# levelshifter.net
KiCad netlist of a schematic drawn in EAGLE
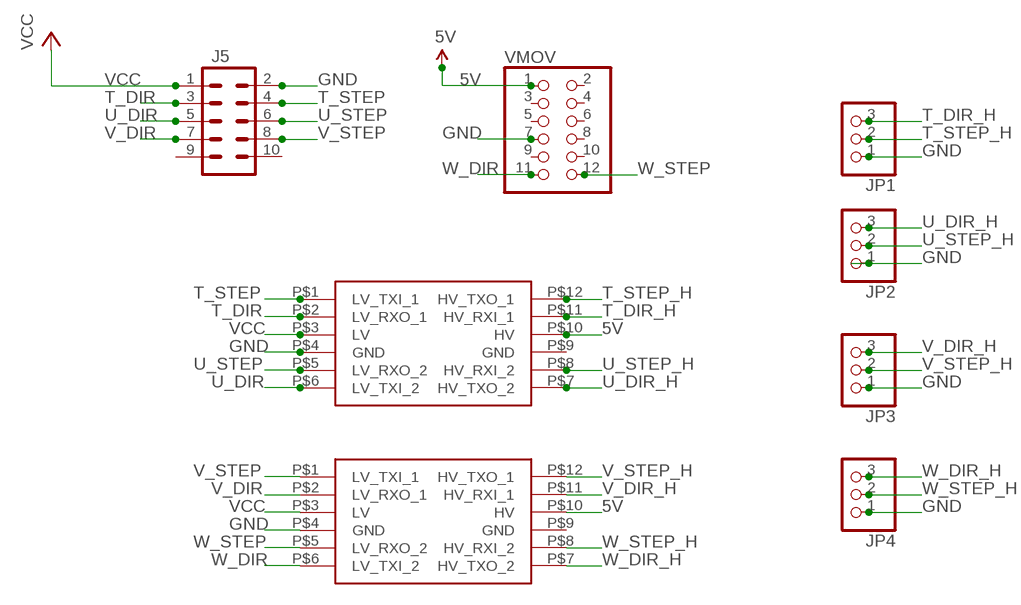
[diagram p0: schematic, sheet 1]

(export (version "E")
  (design (tool "Eeschema 10.0.6"))
  (components
    (comp (ref "CP")
      (value "LOGIC_LEVEL_CONVERTER")
      (footprint "eagle-import:LOGIC_LEVEL_CONVERTER")
      (libsource (lib "eagle-import") (part "LOGIC_LEVEL_CONVERTER"))
    )
    (comp (ref "CP1")
      (value "LOGIC_LEVEL_CONVERTER")
      (footprint "eagle-import:LOGIC_LEVEL_CONVERTER")
      (libsource (lib "eagle-import") (part "LOGIC_LEVEL_CONVERTER"))
    )
    (comp (ref "J5")
      (value "M05X2PTH")
      (footprint "eagle-import:AVR_ICSP")
      (libsource (lib "eagle-import") (part "M05X2PTH"))
    )
    (comp (ref "JP1")
      (value "PINHD-1X3")
      (footprint "eagle-import:1X03")
      (libsource (lib "eagle-import") (part "PINHD-1X3"))
    )
    (comp (ref "JP2")
      (value "PINHD-1X3")
      (footprint "eagle-import:1X03")
      (libsource (lib "eagle-import") (part "PINHD-1X3"))
    )
    (comp (ref "JP3")
      (value "PINHD-1X3")
      (footprint "eagle-import:1X03")
      (libsource (lib "eagle-import") (part "PINHD-1X3"))
    )
    (comp (ref "JP4")
      (value "PINHD-1X3")
      (footprint "eagle-import:1X03")
      (libsource (lib "eagle-import") (part "PINHD-1X3"))
    )
    (comp (ref "VMOV")
      (value "PINHD-2X6")
      (footprint "eagle-import:2X06")
      (libsource (lib "eagle-import") (part "PINHD-2X6"))
    )
  )
  (nets
    (net (code "1") (name "/GND") (class "Default")
      (node (ref "CP") (pin "P$4") (pinfunction "GND_P$4") (pintype "bidirectional"))
      (node (ref "CP1") (pin "P$4") (pinfunction "GND_P$4") (pintype "bidirectional"))
      (node (ref "J5") (pin "2") (pinfunction "2_2") (pintype "passive"))
      (node (ref "JP1") (pin "1") (pinfunction "1_1") (pintype "passive"))
      (node (ref "JP2") (pin "1") (pinfunction "1_1") (pintype "passive"))
      (node (ref "JP3") (pin "1") (pinfunction "1_1") (pintype "passive"))
      (node (ref "JP4") (pin "1") (pinfunction "1_1") (pintype "passive"))
      (node (ref "VMOV") (pin "7") (pinfunction "7_7") (pintype "passive"))
    )
    (net (code "2") (name "/T_DIR") (class "Default")
      (node (ref "CP") (pin "P$2") (pinfunction "LV_RXO_1_P$2") (pintype "bidirectional"))
      (node (ref "J5") (pin "3") (pinfunction "3_3") (pintype "passive"))
    )
    (net (code "3") (name "/T_DIR_H") (class "Default")
      (node (ref "CP") (pin "P$11") (pinfunction "HV_RXI_1_P$11") (pintype "bidirectional"))
      (node (ref "JP1") (pin "3") (pinfunction "3_3") (pintype "passive"))
    )
    (net (code "4") (name "/T_STEP") (class "Default")
      (node (ref "CP") (pin "P$1") (pinfunction "LV_TXI_1_P$1") (pintype "bidirectional"))
      (node (ref "J5") (pin "4") (pinfunction "4_4") (pintype "passive"))
    )
    (net (code "5") (name "/T_STEP_H") (class "Default")
      (node (ref "CP") (pin "P$12") (pinfunction "HV_TXO_1_P$12") (pintype "bidirectional"))
      (node (ref "JP1") (pin "2") (pinfunction "2_2") (pintype "passive"))
    )
    (net (code "6") (name "/U_DIR") (class "Default")
      (node (ref "CP") (pin "P$6") (pinfunction "LV_TXI_2_P$6") (pintype "bidirectional"))
      (node (ref "J5") (pin "5") (pinfunction "5_5") (pintype "passive"))
    )
    (net (code "7") (name "/U_DIR_H") (class "Default")
      (node (ref "CP") (pin "P$7") (pinfunction "HV_TXO_2_P$7") (pintype "bidirectional"))
      (node (ref "JP2") (pin "3") (pinfunction "3_3") (pintype "passive"))
    )
    (net (code "8") (name "/U_STEP") (class "Default")
      (node (ref "CP") (pin "P$5") (pinfunction "LV_RXO_2_P$5") (pintype "bidirectional"))
      (node (ref "J5") (pin "6") (pinfunction "6_6") (pintype "passive"))
    )
    (net (code "9") (name "/U_STEP_H") (class "Default")
      (node (ref "CP") (pin "P$8") (pinfunction "HV_RXI_2_P$8") (pintype "bidirectional"))
      (node (ref "JP2") (pin "2") (pinfunction "2_2") (pintype "passive"))
    )
    (net (code "10") (name "/V_DIR") (class "Default")
      (node (ref "CP1") (pin "P$2") (pinfunction "LV_RXO_1_P$2") (pintype "bidirectional"))
      (node (ref "J5") (pin "7") (pinfunction "7_7") (pintype "passive"))
    )
    (net (code "11") (name "/V_DIR_H") (class "Default")
      (node (ref "CP1") (pin "P$11") (pinfunction "HV_RXI_1_P$11") (pintype "bidirectional"))
      (node (ref "JP3") (pin "3") (pinfunction "3_3") (pintype "passive"))
    )
    (net (code "12") (name "/V_STEP") (class "Default")
      (node (ref "CP1") (pin "P$1") (pinfunction "LV_TXI_1_P$1") (pintype "bidirectional"))
      (node (ref "J5") (pin "8") (pinfunction "8_8") (pintype "passive"))
    )
    (net (code "13") (name "/V_STEP_H") (class "Default")
      (node (ref "CP1") (pin "P$12") (pinfunction "HV_TXO_1_P$12") (pintype "bidirectional"))
      (node (ref "JP3") (pin "2") (pinfunction "2_2") (pintype "passive"))
    )
    (net (code "14") (name "/W_DIR") (class "Default")
      (node (ref "CP1") (pin "P$6") (pinfunction "LV_TXI_2_P$6") (pintype "bidirectional"))
      (node (ref "VMOV") (pin "11") (pinfunction "11_11") (pintype "passive"))
    )
    (net (code "15") (name "/W_DIR_H") (class "Default")
      (node (ref "CP1") (pin "P$7") (pinfunction "HV_TXO_2_P$7") (pintype "bidirectional"))
      (node (ref "JP4") (pin "3") (pinfunction "3_3") (pintype "passive"))
    )
    (net (code "16") (name "/W_STEP") (class "Default")
      (node (ref "CP1") (pin "P$5") (pinfunction "LV_RXO_2_P$5") (pintype "bidirectional"))
      (node (ref "VMOV") (pin "12") (pinfunction "12_12") (pintype "passive"))
    )
    (net (code "17") (name "/W_STEP_H") (class "Default")
      (node (ref "CP1") (pin "P$8") (pinfunction "HV_RXI_2_P$8") (pintype "bidirectional"))
      (node (ref "JP4") (pin "2") (pinfunction "2_2") (pintype "passive"))
    )
    (net (code "18") (name "5V") (class "Default")
      (node (ref "CP") (pin "P$10") (pinfunction "HV_P$10") (pintype "bidirectional"))
      (node (ref "CP1") (pin "P$10") (pinfunction "HV_P$10") (pintype "bidirectional"))
      (node (ref "VMOV") (pin "1") (pinfunction "1_1") (pintype "passive"))
    )
    (net (code "19") (name "VCC") (class "Default")
      (node (ref "CP") (pin "P$3") (pinfunction "LV_P$3") (pintype "bidirectional"))
      (node (ref "CP1") (pin "P$3") (pinfunction "LV_P$3") (pintype "bidirectional"))
      (node (ref "J5") (pin "1") (pinfunction "1_1") (pintype "passive"))
    )
    (net (code "20") (name "unconnected-(CP-GND-PadP$9)") (class "Default")
      (node (ref "CP") (pin "P$9") (pinfunction "GND_P$9") (pintype "bidirectional"))
    )
    (net (code "21") (name "unconnected-(CP1-GND-PadP$9)") (class "Default")
      (node (ref "CP1") (pin "P$9") (pinfunction "GND_P$9") (pintype "bidirectional"))
    )
    (net (code "22") (name "unconnected-(J5-Pad9)") (class "Default")
      (node (ref "J5") (pin "9") (pinfunction "9_9") (pintype "passive"))
    )
    (net (code "23") (name "unconnected-(J5-Pad10)") (class "Default")
      (node (ref "J5") (pin "10") (pinfunction "10_10") (pintype "passive"))
    )
    (net (code "24") (name "unconnected-(VMOV-Pad2)") (class "Default")
      (node (ref "VMOV") (pin "2") (pinfunction "2_2") (pintype "passive"))
    )
    (net (code "25") (name "unconnected-(VMOV-Pad3)") (class "Default")
      (node (ref "VMOV") (pin "3") (pinfunction "3_3") (pintype "passive"))
    )
    (net (code "26") (name "unconnected-(VMOV-Pad4)") (class "Default")
      (node (ref "VMOV") (pin "4") (pinfunction "4_4") (pintype "passive"))
    )
    (net (code "27") (name "unconnected-(VMOV-Pad5)") (class "Default")
      (node (ref "VMOV") (pin "5") (pinfunction "5_5") (pintype "passive"))
    )
    (net (code "28") (name "unconnected-(VMOV-Pad6)") (class "Default")
      (node (ref "VMOV") (pin "6") (pinfunction "6_6") (pintype "passive"))
    )
    (net (code "29") (name "unconnected-(VMOV-Pad8)") (class "Default")
      (node (ref "VMOV") (pin "8") (pinfunction "8_8") (pintype "passive"))
    )
    (net (code "30") (name "unconnected-(VMOV-Pad9)") (class "Default")
      (node (ref "VMOV") (pin "9") (pinfunction "9_9") (pintype "passive"))
    )
    (net (code "31") (name "unconnected-(VMOV-Pad10)") (class "Default")
      (node (ref "VMOV") (pin "10") (pinfunction "10_10") (pintype "passive"))
    )
  )
)
